# Power.net
KiCad netlist of a schematic drawn in Altium Designer
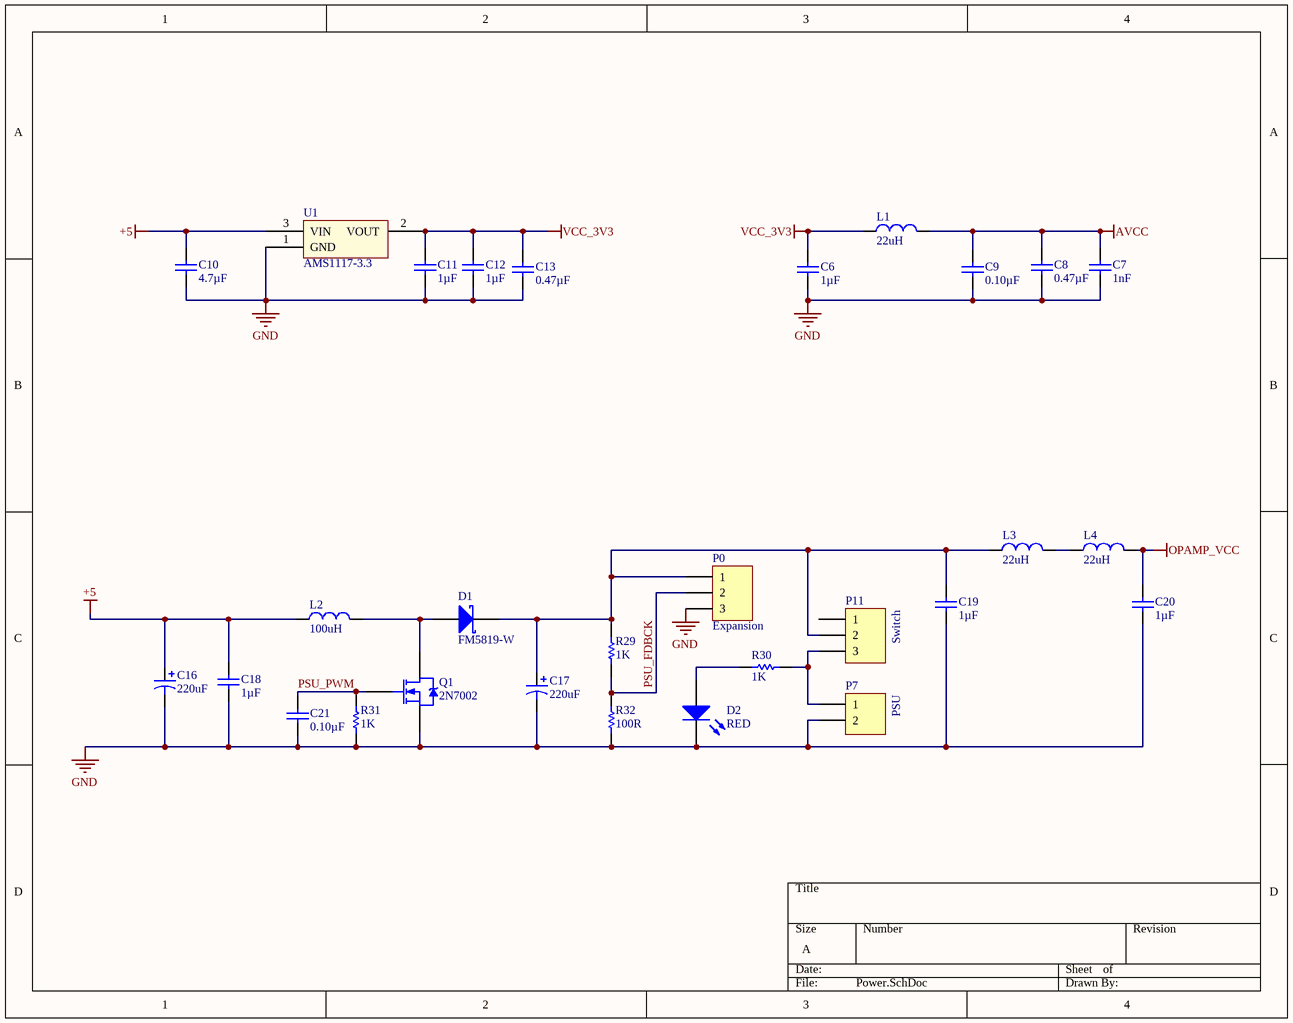
[diagram p0: Power.SchDoc]

(export (version "E")
  (design (tool "Eeschema 10.0.6"))
  (components
    (comp (ref "C6")
      (value "1µF")
      (footprint "CAPC200X125X75L45N")
      (description "1µF 25V Ceramic Capacitor X5R 0805 (2012 Metric) 0.079\" L x 0.049\" W (2.00mm x 1.25mm)")
      (fields
        (field (name "MANUFACTURER") "Wurth Electronics")
        (field (name "MANUFACTURER PART NUMBER") "885012107015")
      )
      (libsource (lib "labrador") (part "885012107015"))
    )
    (comp (ref "C7")
      (value "1nF")
      (footprint "CAPC200X125X75L45N")
      (description "1000pF 16V Ceramic Capacitor X7R 0805 (2012 Metric) 0.079\" L x 0.049\" W (2.00mm x 1.25mm)")
      (fields
        (field (name "MANUFACTURER") "Wurth Electronics")
        (field (name "MANUFACTURER PART NUMBER") "885012207033")
      )
      (libsource (lib "labrador") (part "885012207033"))
    )
    (comp (ref "C8")
      (value "0.47µF")
      (footprint "CAPC200X125X75L45N")
      (description "0.47µF 10V Ceramic Capacitor X7R 0805 (2012 Metric) 0.079\" L x 0.049\" W (2.00mm x 1.25mm)")
      (fields
        (field (name "MANUFACTURER") "Wurth Electronics")
        (field (name "MANUFACTURER PART NUMBER") "885012207020")
      )
      (libsource (lib "labrador") (part "885012207020"))
    )
    (comp (ref "C9")
      (value "0.10µF")
      (footprint "CAPC200X125X75L45N")
      (description "0.10µF 10V Ceramic Capacitor X7R 0805 (2012 Metric) 0.079\" L x 0.049\" W (2.00mm x 1.25mm)")
      (fields
        (field (name "MANUFACTURER") "Wurth Electronics")
        (field (name "MANUFACTURER PART NUMBER") "885012207016")
      )
      (libsource (lib "labrador") (part "885012207016"))
    )
    (comp (ref "C10")
      (value "4.7µF")
      (footprint "CAPC200X125X75L45N")
      (description "4.7µF 16V Ceramic Capacitor X5R 0805 (2012 Metric) 0.079\" L x 0.049\" W (2.00mm x 1.25mm)")
      (fields
        (field (name "MANUFACTURER") "Wurth Electronics")
        (field (name "MANUFACTURER PART NUMBER") "885012107013")
      )
      (libsource (lib "labrador") (part "885012107013"))
    )
    (comp (ref "C11")
      (value "1µF")
      (footprint "CAPC200X125X75L45N")
      (description "1µF 25V Ceramic Capacitor X5R 0805 (2012 Metric) 0.079\" L x 0.049\" W (2.00mm x 1.25mm)")
      (fields
        (field (name "MANUFACTURER") "Wurth Electronics")
        (field (name "MANUFACTURER PART NUMBER") "885012107015")
      )
      (libsource (lib "labrador") (part "885012107015"))
    )
    (comp (ref "C12")
      (value "1µF")
      (footprint "CAPC200X125X75L45N")
      (description "1µF 25V Ceramic Capacitor X5R 0805 (2012 Metric) 0.079\" L x 0.049\" W (2.00mm x 1.25mm)")
      (fields
        (field (name "MANUFACTURER") "Wurth Electronics")
        (field (name "MANUFACTURER PART NUMBER") "885012107015")
      )
      (libsource (lib "labrador") (part "885012107015"))
    )
    (comp (ref "C13")
      (value "0.47µF")
      (footprint "CAPC200X125X75L45N")
      (description "0.47µF 10V Ceramic Capacitor X7R 0805 (2012 Metric) 0.079\" L x 0.049\" W (2.00mm x 1.25mm)")
      (fields
        (field (name "MANUFACTURER") "Wurth Electronics")
        (field (name "MANUFACTURER PART NUMBER") "885012207020")
      )
      (libsource (lib "labrador") (part "885012207020"))
    )
    (comp (ref "C16")
      (value "220uF")
      (footprint "Cap_Elec_47uF")
      (description "Aluminium Electrolyte 16V max")
      (fields (field (name "Comment") "CAP_POLAR"))
      (libsource (lib "labrador") (part "CAP_POLAR"))
    )
    (comp (ref "C17")
      (value "220uF")
      (footprint "Cap_Elec_47uF")
      (description "Aluminium Electrolyte 16V max")
      (fields (field (name "Comment") "CAP_POLAR"))
      (libsource (lib "labrador") (part "CAP_POLAR"))
    )
    (comp (ref "C18")
      (value "1µF")
      (footprint "CAPC200X125X75L45N")
      (description "1µF 25V Ceramic Capacitor X5R 0805 (2012 Metric) 0.079\" L x 0.049\" W (2.00mm x 1.25mm)")
      (fields
        (field (name "MANUFACTURER") "Wurth Electronics")
        (field (name "MANUFACTURER PART NUMBER") "885012107015")
      )
      (libsource (lib "labrador") (part "885012107015"))
    )
    (comp (ref "C19")
      (value "1µF")
      (footprint "CAPC200X125X75L45N")
      (description "1µF 25V Ceramic Capacitor X5R 0805 (2012 Metric) 0.079\" L x 0.049\" W (2.00mm x 1.25mm)")
      (fields
        (field (name "MANUFACTURER") "Wurth Electronics")
        (field (name "MANUFACTURER PART NUMBER") "885012107015")
      )
      (libsource (lib "labrador") (part "885012107015"))
    )
    (comp (ref "C20")
      (value "1µF")
      (footprint "CAPC200X125X75L45N")
      (description "1µF 25V Ceramic Capacitor X5R 0805 (2012 Metric) 0.079\" L x 0.049\" W (2.00mm x 1.25mm)")
      (fields
        (field (name "MANUFACTURER") "Wurth Electronics")
        (field (name "MANUFACTURER PART NUMBER") "885012107015")
      )
      (libsource (lib "labrador") (part "885012107015"))
    )
    (comp (ref "C21")
      (value "0.10µF")
      (footprint "CAPC200X125X75L45N")
      (description "0.10µF 10V Ceramic Capacitor X7R 0805 (2012 Metric) 0.079\" L x 0.049\" W (2.00mm x 1.25mm)")
      (fields
        (field (name "MANUFACTURER") "Wurth Electronics")
        (field (name "MANUFACTURER PART NUMBER") "885012207016")
      )
      (libsource (lib "labrador") (part "885012207016"))
    )
    (comp (ref "D1")
      (value "FM5819-W")
      (footprint "DIOM470X266X220L114X139N")
      (description "Schottky Diodes & Rectifiers Vr/40V Io/1A T/R")
      (fields (field (name "MANUFACTURER") "Rectron"))
      (libsource (lib "labrador") (part "FM5819-W"))
    )
    (comp (ref "D2")
      (value "RED")
      (footprint "LEDC200X125X38L45N")
      (description "LED RED DIFFUSED 0805 SMD")
      (fields
        (field (name "MANUFACTURER") "OSRAM Opto Semiconductors Inc.")
        (field (name "MANUFACTURER PART NUMBER") "LH R974-LP-1")
      )
      (libsource (lib "labrador") (part "LH R974-LP-1"))
    )
    (comp (ref "L1")
      (value "22uH")
      (footprint "CAPC200X125X140L45N")
      (description "Fixed Inductor 22uH 20% 165mA")
      (libsource (lib "labrador") (part "LBC2016T220M"))
    )
    (comp (ref "L2")
      (value "100uH")
      (footprint "CD54-Modified")
      (description "FIXED IND 100uH 400MA 1.26 OHM")
      (fields
        (field (name "MANUFACTURER") "Sumida America Components Inc.")
        (field (name "MANUFACTURER PART NUMBER") "CD75NP-331KC")
      )
      (libsource (lib "labrador") (part "CD75NP-331KC"))
    )
    (comp (ref "L3")
      (value "22uH")
      (footprint "CAPC200X125X140L45N")
      (description "Fixed Inductor 22uH 20% 165mA")
      (libsource (lib "labrador") (part "LBC2016T220M"))
    )
    (comp (ref "L4")
      (value "22uH")
      (footprint "CAPC200X125X140L45N")
      (description "Fixed Inductor 22uH 20% 165mA")
      (libsource (lib "labrador") (part "LBC2016T220M"))
    )
    (comp (ref "P0")
      (value "Expansion")
      (footprint "HDR1X3")
      (description "Header, 3-Pin")
      (fields (field (name "PUBLISHER") "Altium Limited"))
      (libsource (lib "labrador") (part "Header 3"))
    )
    (comp (ref "P7")
      (value "PSU")
      (footprint "HDR1X2")
      (description "Header, 2-Pin")
      (fields (field (name "PUBLISHER") "Altium Limited"))
      (libsource (lib "labrador") (part "Header 2"))
    )
    (comp (ref "P11")
      (value "Switch")
      (footprint "HDR1X3")
      (description "Header, 3-Pin")
      (fields (field (name "PUBLISHER") "Altium Limited"))
      (libsource (lib "labrador") (part "Header 3"))
    )
    (comp (ref "Q1")
      (value "2N7002")
      (footprint "SOT23-3P95_230X110L30X43N")
      (description "MOSFET N-CH 60V 0.115A SOT-23")
      (fields
        (field (name "MANUFACTURER") "ON Semiconductor")
        (field (name "MANUFACTURER PART NUMBER") "2N7002LT1G")
      )
      (libsource (lib "labrador") (part "2N7002LT1G"))
    )
    (comp (ref "R29")
      (value "1K")
      (footprint "RESC200X125X50L35N")
      (description "RES SMD 1K OHM 1% 1/8W 0805")
      (fields
        (field (name "MANUFACTURER") "Yageo")
        (field (name "MANUFACTURER PART NUMBER") "RC0805FR-071KL")
      )
      (libsource (lib "labrador") (part "RC0805FR-071KL"))
    )
    (comp (ref "R30")
      (value "1K")
      (footprint "RESC200X125X50L35N")
      (description "RES SMD 1K OHM 1% 1/8W 0805")
      (fields
        (field (name "MANUFACTURER") "Yageo")
        (field (name "MANUFACTURER PART NUMBER") "RC0805FR-071KL")
      )
      (libsource (lib "labrador") (part "RC0805FR-071KL"))
    )
    (comp (ref "R31")
      (value "1K")
      (footprint "RESC200X125X50L35N")
      (description "RES SMD 1K OHM 1% 1/8W 0805")
      (fields
        (field (name "MANUFACTURER") "Yageo")
        (field (name "MANUFACTURER PART NUMBER") "RC0805FR-071KL")
      )
      (libsource (lib "labrador") (part "RC0805FR-071KL"))
    )
    (comp (ref "R32")
      (value "100R")
      (footprint "RESC200X125X50L35N")
      (description "YAGEO         RC0805JR-07100RL             RES, THICK FILM, 100R, 5%, 0.125W, 0805")
      (fields
        (field (name "MANUFACTURER") "Yageo")
        (field (name "MANUFACTURER PART NUMBER") "RC0805JR-07100RL")
      )
      (libsource (lib "labrador") (part "RC0805JR-07100RL"))
    )
    (comp (ref "U1")
      (value "AMS1117-3.3")
      (footprint "SOT223-4P229_700X180L36X74N")
      (description "Linear Reg 3.3, 1.2V dropout")
      (libsource (lib "labrador") (part "AMS1117-3.3"))
    )
  )
  (nets
    (net (code "1") (name "+5") (class "Default")
      (node (ref "C10") (pin "2") (pinfunction "2_2") (pintype "passive"))
      (node (ref "C16") (pin "2") (pinfunction "2_2") (pintype "passive"))
      (node (ref "C18") (pin "2") (pinfunction "2_2") (pintype "passive"))
      (node (ref "L2") (pin "1") (pinfunction "1_1") (pintype "passive"))
      (node (ref "U1") (pin "3") (pinfunction "VIN_3") (pintype "power_in"))
    )
    (net (code "2") (name "/PSU_FDBCK") (class "Default")
      (node (ref "P0") (pin "2") (pinfunction "2_2") (pintype "passive"))
      (node (ref "R29") (pin "1") (pinfunction "1_1") (pintype "passive"))
      (node (ref "R32") (pin "2") (pinfunction "2_2") (pintype "passive"))
    )
    (net (code "3") (name "/PSU_PWM") (class "Default")
      (node (ref "C21") (pin "2") (pinfunction "2_2") (pintype "passive"))
      (node (ref "Q1") (pin "1") (pinfunction "G_1") (pintype "passive"))
      (node (ref "R31") (pin "2") (pinfunction "2_2") (pintype "passive"))
    )
    (net (code "4") (name "AVCC") (class "Default")
      (node (ref "C7") (pin "2") (pinfunction "2_2") (pintype "passive"))
      (node (ref "C8") (pin "2") (pinfunction "2_2") (pintype "passive"))
      (node (ref "C9") (pin "2") (pinfunction "2_2") (pintype "passive"))
      (node (ref "L1") (pin "2") (pinfunction "2_2") (pintype "passive"))
    )
    (net (code "5") (name "GND") (class "Default")
      (node (ref "C10") (pin "1") (pinfunction "1_1") (pintype "passive"))
      (node (ref "C11") (pin "1") (pinfunction "1_1") (pintype "passive"))
      (node (ref "C12") (pin "1") (pinfunction "1_1") (pintype "passive"))
      (node (ref "C13") (pin "1") (pinfunction "1_1") (pintype "passive"))
      (node (ref "C16") (pin "1") (pinfunction "1_1") (pintype "passive"))
      (node (ref "C17") (pin "1") (pinfunction "1_1") (pintype "passive"))
      (node (ref "C18") (pin "1") (pinfunction "1_1") (pintype "passive"))
      (node (ref "C19") (pin "1") (pinfunction "1_1") (pintype "passive"))
      (node (ref "C20") (pin "1") (pinfunction "1_1") (pintype "passive"))
      (node (ref "C21") (pin "1") (pinfunction "1_1") (pintype "passive"))
      (node (ref "C6") (pin "1") (pinfunction "1_1") (pintype "passive"))
      (node (ref "C7") (pin "1") (pinfunction "1_1") (pintype "passive"))
      (node (ref "C8") (pin "1") (pinfunction "1_1") (pintype "passive"))
      (node (ref "C9") (pin "1") (pinfunction "1_1") (pintype "passive"))
      (node (ref "D2") (pin "C") (pinfunction "K_C") (pintype "passive"))
      (node (ref "P0") (pin "3") (pinfunction "3_3") (pintype "passive"))
      (node (ref "P7") (pin "2") (pinfunction "2_2") (pintype "passive"))
      (node (ref "Q1") (pin "2") (pinfunction "S_2") (pintype "passive"))
      (node (ref "R31") (pin "1") (pinfunction "1_1") (pintype "passive"))
      (node (ref "R32") (pin "1") (pinfunction "1_1") (pintype "passive"))
      (node (ref "U1") (pin "1") (pinfunction "GND_1") (pintype "power_in"))
    )
    (net (code "6") (name "Net-(C17-Pad2)") (class "Default")
      (node (ref "C17") (pin "2") (pinfunction "2_2") (pintype "passive"))
      (node (ref "C19") (pin "2") (pinfunction "2_2") (pintype "passive"))
      (node (ref "D1") (pin "C") (pinfunction "C_C") (pintype "passive"))
      (node (ref "L3") (pin "1") (pinfunction "1_1") (pintype "passive"))
      (node (ref "P0") (pin "1") (pinfunction "1_1") (pintype "passive"))
      (node (ref "P11") (pin "2") (pinfunction "2_2") (pintype "passive"))
      (node (ref "R29") (pin "2") (pinfunction "2_2") (pintype "passive"))
    )
    (net (code "7") (name "Net-(D2-PadA)") (class "Default")
      (node (ref "D2") (pin "A") (pinfunction "A_A") (pintype "passive"))
      (node (ref "R30") (pin "1") (pinfunction "1_1") (pintype "passive"))
    )
    (net (code "8") (name "Net-(L3-Pad2)") (class "Default")
      (node (ref "L3") (pin "2") (pinfunction "2_2") (pintype "passive"))
      (node (ref "L4") (pin "1") (pinfunction "1_1") (pintype "passive"))
    )
    (net (code "9") (name "Net-(P11-Pad3)") (class "Default")
      (node (ref "P11") (pin "3") (pinfunction "3_3") (pintype "passive"))
      (node (ref "P7") (pin "1") (pinfunction "1_1") (pintype "passive"))
      (node (ref "R30") (pin "2") (pinfunction "2_2") (pintype "passive"))
    )
    (net (code "10") (name "Net-(Q1-D)") (class "Default")
      (node (ref "D1") (pin "A") (pinfunction "A_A") (pintype "passive"))
      (node (ref "L2") (pin "2") (pinfunction "2_2") (pintype "passive"))
      (node (ref "Q1") (pin "3") (pinfunction "D_3") (pintype "passive"))
    )
    (net (code "11") (name "OPAMP_VCC") (class "Default")
      (node (ref "C20") (pin "2") (pinfunction "2_2") (pintype "passive"))
      (node (ref "L4") (pin "2") (pinfunction "2_2") (pintype "passive"))
    )
    (net (code "12") (name "VCC_3V3") (class "Default")
      (node (ref "C11") (pin "2") (pinfunction "2_2") (pintype "passive"))
      (node (ref "C12") (pin "2") (pinfunction "2_2") (pintype "passive"))
      (node (ref "C13") (pin "2") (pinfunction "2_2") (pintype "passive"))
      (node (ref "C6") (pin "2") (pinfunction "2_2") (pintype "passive"))
      (node (ref "L1") (pin "1") (pinfunction "1_1") (pintype "passive"))
      (node (ref "U1") (pin "2") (pinfunction "VOUT_2") (pintype "power_in"))
    )
    (net (code "13") (name "unconnected-(P11-Pad1)") (class "Default")
      (node (ref "P11") (pin "1") (pinfunction "1_1") (pintype "passive"))
    )
  )
)
